# SparkFun_PIR_Breakout.net
KiCad netlist of a schematic drawn in EAGLE
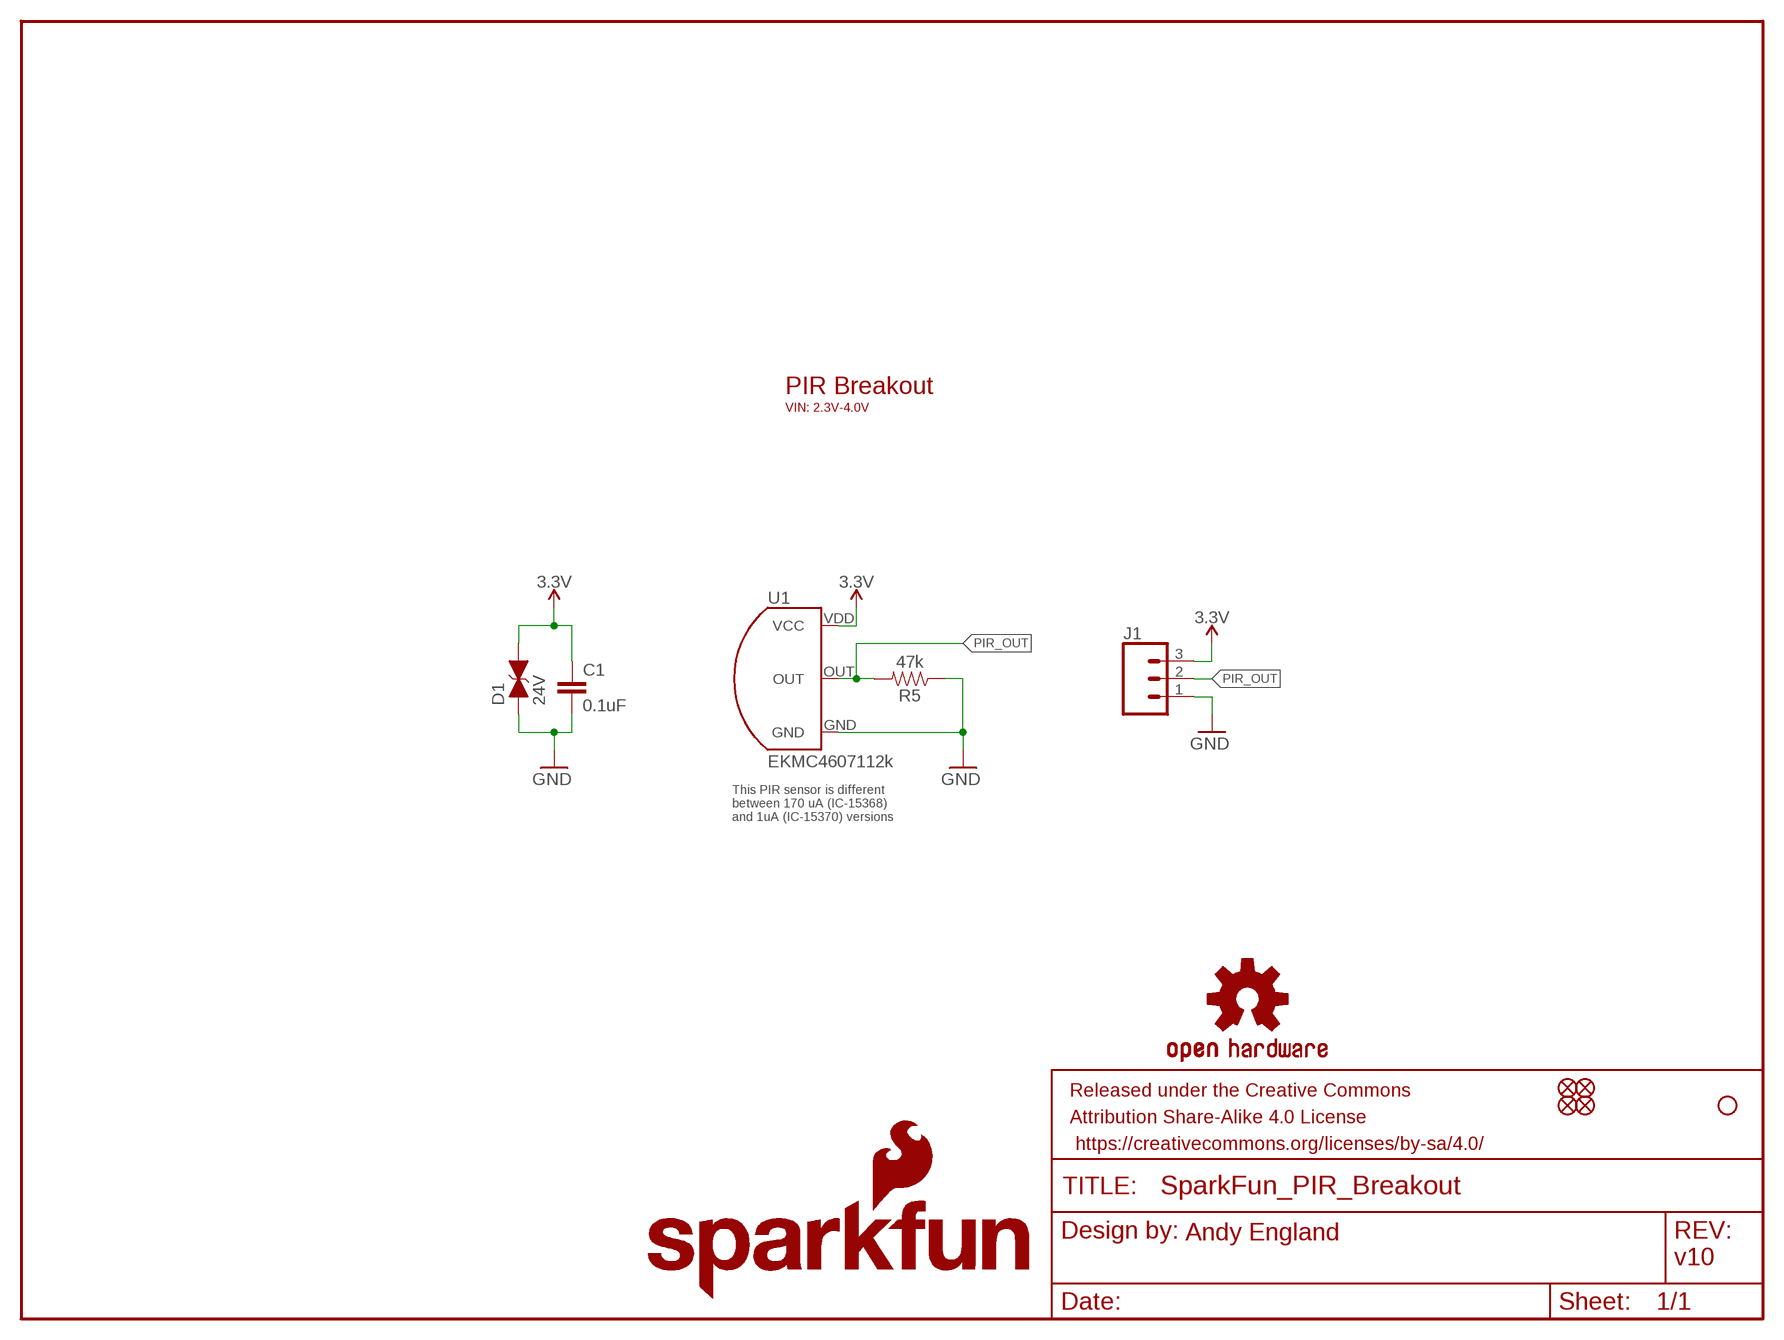
[diagram p0: schematic, sheet 1]

(export (version "E")
  (design (tool "Eeschema 10.0.6"))
  (components
    (comp (ref "C1")
      (value "0.1uF")
      (footprint "eagle-import:0603")
      (libsource (lib "eagle-import") (part "0.1UF-0603-25V-(+80/-20%)"))
    )
    (comp (ref "D1")
      (value "24V")
      (footprint "eagle-import:0603")
      (libsource (lib "eagle-import") (part "DIODE_TVS"))
    )
    (comp (ref "FRAME1")
      (value "FRAME-LETTER")
      (footprint "eagle-import:CREATIVE_COMMONS")
      (libsource (lib "eagle-import") (part "FRAME-LETTER"))
    )
    (comp (ref "H1")
      (value "STAND-OFF")
      (footprint "eagle-import:STAND-OFF")
      (libsource (lib "eagle-import") (part "STAND-OFF"))
    )
    (comp (ref "J1")
      (value "CONN_031X03_NO_SILK")
      (footprint "eagle-import:1X03_NO_SILK")
      (libsource (lib "eagle-import") (part "CONN_031X03_NO_SILK"))
    )
    (comp (ref "JP2")
      (value "FIDUCIALUFIDUCIAL")
      (footprint "eagle-import:MICRO-FIDUCIAL")
      (libsource (lib "eagle-import") (part "FIDUCIALUFIDUCIAL"))
    )
    (comp (ref "JP6")
      (value "FIDUCIALUFIDUCIAL")
      (footprint "eagle-import:MICRO-FIDUCIAL")
      (libsource (lib "eagle-import") (part "FIDUCIALUFIDUCIAL"))
    )
    (comp (ref "JP8")
      (value "FIDUCIALUFIDUCIAL")
      (footprint "eagle-import:MICRO-FIDUCIAL")
      (libsource (lib "eagle-import") (part "FIDUCIALUFIDUCIAL"))
    )
    (comp (ref "JP9")
      (value "FIDUCIALUFIDUCIAL")
      (footprint "eagle-import:MICRO-FIDUCIAL")
      (libsource (lib "eagle-import") (part "FIDUCIALUFIDUCIAL"))
    )
    (comp (ref "LOGO1")
      (value "OSHW-LOGOMINI")
      (footprint "eagle-import:OSHW-LOGO-MINI")
      (libsource (lib "eagle-import") (part "OSHW-LOGOMINI"))
    )
    (comp (ref "LOGO3")
      (value "SFE_LOGO_NAME_FLAME.1_INCH")
      (footprint "eagle-import:SFE_LOGO_NAME_FLAME_.1")
      (libsource (lib "eagle-import") (part "SFE_LOGO_NAME_FLAME.1_INCH"))
    )
    (comp (ref "LOGO4")
      (value "SFE_LOGO_FLAME.1_INCH")
      (footprint "eagle-import:SFE_LOGO_FLAME_.1")
      (libsource (lib "eagle-import") (part "SFE_LOGO_FLAME.1_INCH"))
    )
    (comp (ref "R5")
      (value "47k")
      (footprint "eagle-import:0603")
      (libsource (lib "eagle-import") (part "47KOHM-0603-1/10W-1%"))
    )
    (comp (ref "U1")
      (value "EKMC4607112k")
      (footprint "eagle-import:TO-3")
      (libsource (lib "eagle-import") (part "PIR_EKM4607112K"))
    )
  )
  (nets
    (net (code "1") (name "3.3V") (class "Default")
      (node (ref "C1") (pin "1") (pinfunction "1_1") (pintype "passive"))
      (node (ref "D1") (pin "2") (pinfunction "C_2") (pintype "passive"))
      (node (ref "J1") (pin "3") (pinfunction "3_3") (pintype "passive"))
      (node (ref "U1") (pin "VDD") (pinfunction "VCC_VDD") (pintype "bidirectional"))
    )
    (net (code "2") (name "GND") (class "Default")
      (node (ref "C1") (pin "2") (pinfunction "2_2") (pintype "passive"))
      (node (ref "D1") (pin "1") (pinfunction "A_1") (pintype "passive"))
      (node (ref "J1") (pin "1") (pinfunction "1_1") (pintype "passive"))
      (node (ref "R5") (pin "1") (pinfunction "1_1") (pintype "passive"))
      (node (ref "U1") (pin "GND") (pinfunction "GND_GND") (pintype "bidirectional"))
    )
    (net (code "3") (name "PIR_OUT") (class "Default")
      (node (ref "J1") (pin "2") (pinfunction "2_2") (pintype "passive"))
      (node (ref "R5") (pin "2") (pinfunction "2_2") (pintype "passive"))
      (node (ref "U1") (pin "OUT") (pinfunction "OUT_OUT") (pintype "bidirectional"))
    )
  )
)
